# ACS722_Low_Current_Sensor.net
KiCad netlist of a schematic drawn in EAGLE
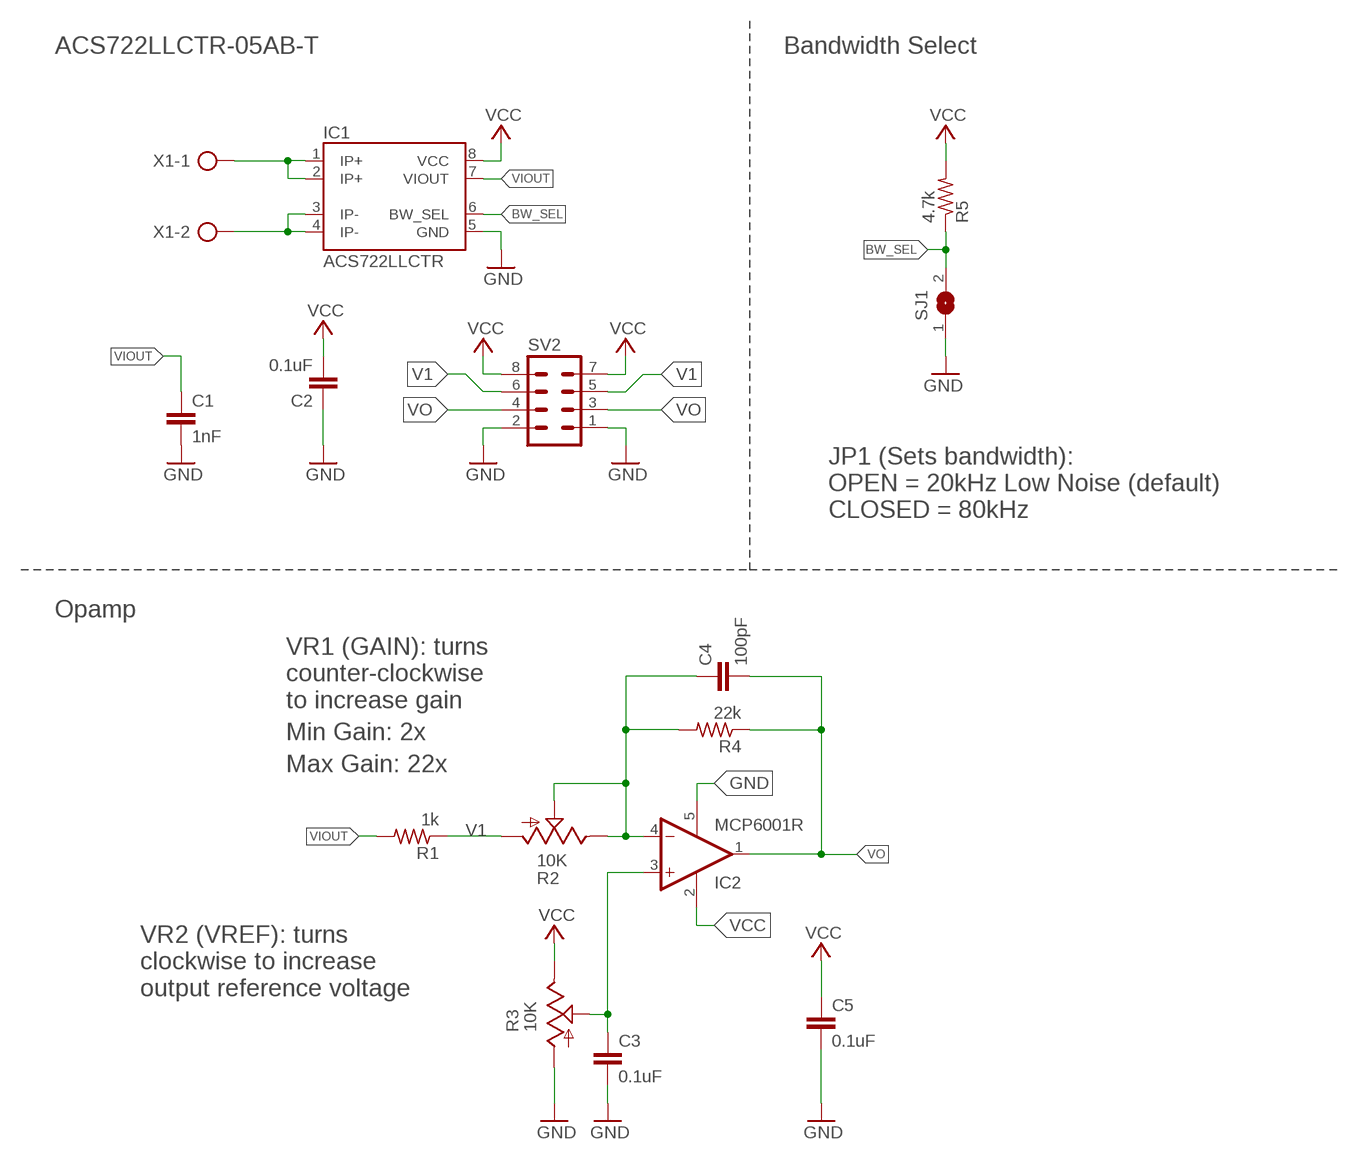
[diagram p0: schematic, sheet 1]

(export (version "E")
  (design (tool "Eeschema 10.0.6"))
  (components
    (comp (ref "C1")
      (value "1nF")
      (footprint "eagle-import:C1206")
      (libsource (lib "eagle-import") (part "C-EUC1206"))
    )
    (comp (ref "C2")
      (value "0.1uF")
      (footprint "eagle-import:C1206")
      (libsource (lib "eagle-import") (part "C-EUC1206"))
    )
    (comp (ref "C3")
      (value "0.1uF")
      (footprint "eagle-import:C1206")
      (libsource (lib "eagle-import") (part "C-EUC1206"))
    )
    (comp (ref "C4")
      (value "100pF")
      (footprint "eagle-import:C1206")
      (libsource (lib "eagle-import") (part "C-EUC1206"))
    )
    (comp (ref "C5")
      (value "0.1uF")
      (footprint "eagle-import:C1206")
      (libsource (lib "eagle-import") (part "C-EUC1206"))
    )
    (comp (ref "IC1")
      (value "ACS722LLCTR")
      (footprint "eagle-import:SO-08")
      (libsource (lib "eagle-import") (part "ACS722LLCTR-05AB-T"))
    )
    (comp (ref "IC2")
      (value "MCP6001R")
      (footprint "eagle-import:SOT23-5")
      (libsource (lib "eagle-import") (part "MCP6001R"))
    )
    (comp (ref "R1")
      (value "1k")
      (footprint "eagle-import:R1206")
      (libsource (lib "eagle-import") (part "R-US_R1206"))
    )
    (comp (ref "R2")
      (value "10K")
      (footprint "eagle-import:CA9V")
      (libsource (lib "eagle-import") (part "TRIM_US-CA9V"))
    )
    (comp (ref "R3")
      (value "10K")
      (footprint "eagle-import:CA9V")
      (libsource (lib "eagle-import") (part "TRIM_US-CA9V"))
    )
    (comp (ref "R4")
      (value "22k")
      (footprint "eagle-import:R1206")
      (libsource (lib "eagle-import") (part "R-US_R1206"))
    )
    (comp (ref "R5")
      (value "4.7k")
      (footprint "eagle-import:R1206")
      (libsource (lib "eagle-import") (part "R-US_R1206"))
    )
    (comp (ref "SJ1") (value "SJ") (footprint "eagle-import:SJ") (libsource (lib "eagle-import") (part "SJ")))
    (comp (ref "SV2")
      (value "MA04-2")
      (footprint "eagle-import:MA04-2")
      (libsource (lib "eagle-import") (part "MA04-2"))
    )
    (comp (ref "X1")
      (value "AK500/2")
      (footprint "eagle-import:AK500_2")
      (libsource (lib "eagle-import") (part "AK500/2"))
    )
  )
  (nets
    (net (code "1") (name "BW_SEL") (class "Default")
      (node (ref "IC1") (pin "6") (pinfunction "BW_SEL_6") (pintype "bidirectional"))
      (node (ref "R5") (pin "1") (pinfunction "1_1") (pintype "passive"))
      (node (ref "SJ1") (pin "2") (pinfunction "2_2") (pintype "passive"))
    )
    (net (code "2") (name "GND") (class "Default")
      (node (ref "C1") (pin "2") (pinfunction "2_2") (pintype "passive"))
      (node (ref "C2") (pin "1") (pinfunction "1_1") (pintype "passive"))
      (node (ref "C3") (pin "2") (pinfunction "2_2") (pintype "passive"))
      (node (ref "C5") (pin "2") (pinfunction "2_2") (pintype "passive"))
      (node (ref "IC1") (pin "5") (pinfunction "GND_5") (pintype "power_in"))
      (node (ref "IC2") (pin "5") (pinfunction "V-_5") (pintype "power_in"))
      (node (ref "R3") (pin "A") (pinfunction "A_A") (pintype "passive"))
      (node (ref "SJ1") (pin "1") (pinfunction "1_1") (pintype "passive"))
      (node (ref "SV2") (pin "1") (pinfunction "1_1") (pintype "passive"))
      (node (ref "SV2") (pin "2") (pinfunction "2_2") (pintype "passive"))
    )
    (net (code "3") (name "Net-(IC2-+IN)") (class "Default")
      (node (ref "C3") (pin "1") (pinfunction "1_1") (pintype "passive"))
      (node (ref "IC2") (pin "3") (pinfunction "+IN_3") (pintype "input"))
      (node (ref "R3") (pin "S") (pinfunction "S_S") (pintype "passive"))
    )
    (net (code "4") (name "Net-(IC2--IN)") (class "Default")
      (node (ref "C4") (pin "1") (pinfunction "1_1") (pintype "passive"))
      (node (ref "IC2") (pin "4") (pinfunction "-IN_4") (pintype "input"))
      (node (ref "R2") (pin "E") (pinfunction "E_E") (pintype "passive"))
      (node (ref "R2") (pin "S") (pinfunction "S_S") (pintype "passive"))
      (node (ref "R4") (pin "2") (pinfunction "2_2") (pintype "passive"))
    )
    (net (code "5") (name "Net-(X1A-KL)") (class "Default")
      (node (ref "IC1") (pin "1") (pinfunction "IP+_1") (pintype "bidirectional"))
      (node (ref "IC1") (pin "2") (pinfunction "IP+_2") (pintype "bidirectional"))
      (node (ref "X1") (pin "1") (pinfunction "KL_1") (pintype "passive"))
    )
    (net (code "6") (name "Net-(X1B-KL)") (class "Default")
      (node (ref "IC1") (pin "3") (pinfunction "IP-_3") (pintype "bidirectional"))
      (node (ref "IC1") (pin "4") (pinfunction "IP-_4") (pintype "bidirectional"))
      (node (ref "X1") (pin "2") (pinfunction "KL_2") (pintype "passive"))
    )
    (net (code "7") (name "V1") (class "Default")
      (node (ref "R1") (pin "1") (pinfunction "1_1") (pintype "passive"))
      (node (ref "R2") (pin "A") (pinfunction "A_A") (pintype "passive"))
      (node (ref "SV2") (pin "5") (pinfunction "5_5") (pintype "passive"))
      (node (ref "SV2") (pin "6") (pinfunction "6_6") (pintype "passive"))
    )
    (net (code "8") (name "VCC") (class "Default")
      (node (ref "C2") (pin "2") (pinfunction "2_2") (pintype "passive"))
      (node (ref "C5") (pin "1") (pinfunction "1_1") (pintype "passive"))
      (node (ref "IC1") (pin "8") (pinfunction "VCC_8") (pintype "power_in"))
      (node (ref "IC2") (pin "2") (pinfunction "V+_2") (pintype "power_in"))
      (node (ref "R3") (pin "E") (pinfunction "E_E") (pintype "passive"))
      (node (ref "R5") (pin "2") (pinfunction "2_2") (pintype "passive"))
      (node (ref "SV2") (pin "7") (pinfunction "7_7") (pintype "passive"))
      (node (ref "SV2") (pin "8") (pinfunction "8_8") (pintype "passive"))
    )
    (net (code "9") (name "VIOUT") (class "Default")
      (node (ref "C1") (pin "1") (pinfunction "1_1") (pintype "passive"))
      (node (ref "IC1") (pin "7") (pinfunction "VIOUT_7") (pintype "bidirectional"))
      (node (ref "R1") (pin "2") (pinfunction "2_2") (pintype "passive"))
    )
    (net (code "10") (name "VO") (class "Default")
      (node (ref "C4") (pin "2") (pinfunction "2_2") (pintype "passive"))
      (node (ref "IC2") (pin "1") (pinfunction "OUT_1") (pintype "output"))
      (node (ref "R4") (pin "1") (pinfunction "1_1") (pintype "passive"))
      (node (ref "SV2") (pin "3") (pinfunction "3_3") (pintype "passive"))
      (node (ref "SV2") (pin "4") (pinfunction "4_4") (pintype "passive"))
    )
  )
)
